# Slave.net
KiCad netlist of a schematic drawn in EAGLE
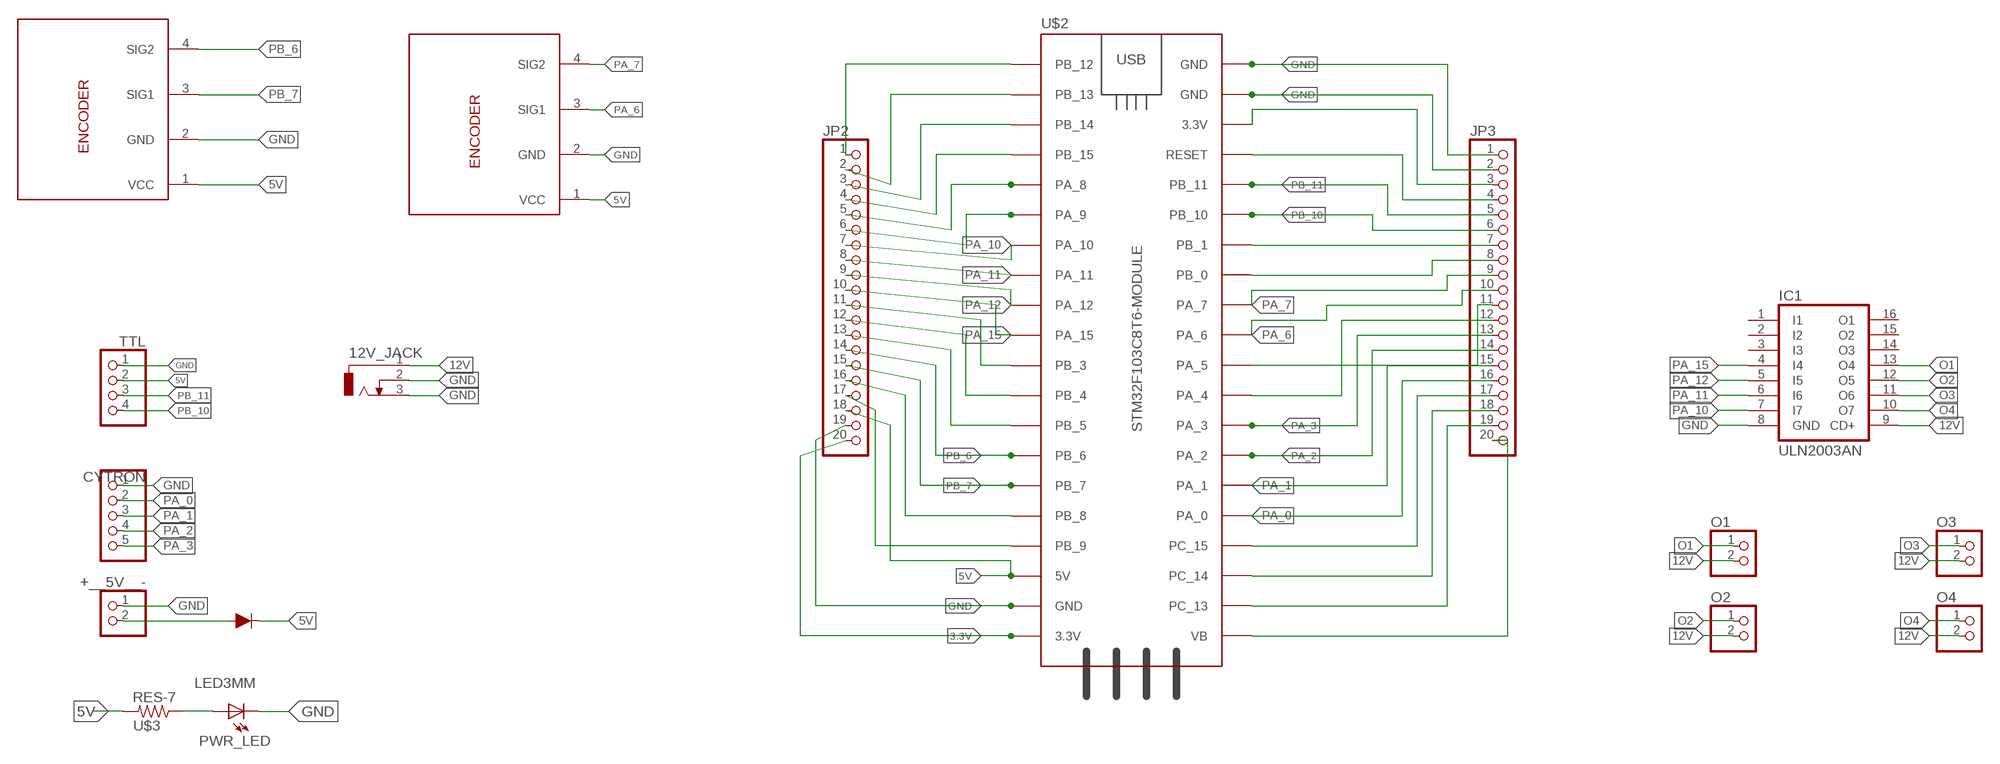
[diagram p0: schematic, sheet 1]

(export (version "E")
  (design (tool "Eeschema 10.0.6"))
  (components
    (comp (ref "+__5V__-")
      (value "PINHD-2_DATA")
      (footprint "eagle-import:1X02_DATA")
      (libsource (lib "eagle-import") (part "PINHD-2_DATA"))
    )
    (comp (ref "12V_JACK")
      (value "CON_JACK")
      (footprint "eagle-import:DCJ0303")
      (libsource (lib "eagle-import") (part "CON_JACK"))
    )
    (comp (ref "CYTRON")
      (value "PINHD-5_DATA")
      (footprint "eagle-import:1X05_DATA")
      (libsource (lib "eagle-import") (part "PINHD-5_DATA"))
    )
    (comp (ref "D1")
      (value "200mA/100V/1V")
      (footprint "eagle-import:DIODE-1N4148")
      (libsource (lib "eagle-import") (part "DIODE(1A)-1N4148"))
    )
    (comp (ref "IC1")
      (value "ULN2003AN")
      (footprint "eagle-import:DIL16")
      (libsource (lib "eagle-import") (part "ULN2003AN"))
    )
    (comp (ref "JP2")
      (value "PINHD-1X20")
      (footprint "eagle-import:1X20")
      (libsource (lib "eagle-import") (part "PINHD-1X20"))
    )
    (comp (ref "JP3")
      (value "PINHD-1X20")
      (footprint "eagle-import:1X20")
      (libsource (lib "eagle-import") (part "PINHD-1X20"))
    )
    (comp (ref "O1")
      (value "PINHD-2_DATA")
      (footprint "eagle-import:1X02_DATA")
      (libsource (lib "eagle-import") (part "PINHD-2_DATA"))
    )
    (comp (ref "O2")
      (value "PINHD-2_DATA")
      (footprint "eagle-import:1X02_DATA")
      (libsource (lib "eagle-import") (part "PINHD-2_DATA"))
    )
    (comp (ref "O3")
      (value "PINHD-2_DATA")
      (footprint "eagle-import:1X02_DATA")
      (libsource (lib "eagle-import") (part "PINHD-2_DATA"))
    )
    (comp (ref "O4")
      (value "PINHD-2_DATA")
      (footprint "eagle-import:1X02_DATA")
      (libsource (lib "eagle-import") (part "PINHD-2_DATA"))
    )
    (comp (ref "PWR_LED")
      (value "LED3MM")
      (footprint "eagle-import:LED3MM")
      (libsource (lib "eagle-import") (part "LED3MM"))
    )
    (comp (ref "TTL")
      (value "PINHD-4_DATA")
      (footprint "eagle-import:1X04_DATA")
      (libsource (lib "eagle-import") (part "PINHD-4_DATA"))
    )
    (comp (ref "U$1")
      (value "ENCODER")
      (footprint "eagle-import:1X04_DATA")
      (libsource (lib "eagle-import") (part "ENCODER"))
    )
    (comp (ref "U$2")
      (value "STM32F103C8T6-MODULE")
      (footprint "eagle-import:STM32F103C8T6-MODULE")
      (libsource (lib "eagle-import") (part "STM32F103C8T6-MODULE"))
    )
    (comp (ref "U$3")
      (value "RES-7")
      (footprint "eagle-import:0204_7")
      (libsource (lib "eagle-import") (part "RES-7"))
    )
    (comp (ref "U$5")
      (value "ENCODER")
      (footprint "eagle-import:1X04_DATA")
      (libsource (lib "eagle-import") (part "ENCODER"))
    )
  )
  (nets
    (net (code "1") (name "3.3V") (class "Default")
      (node (ref "JP2") (pin "20") (pinfunction "20_20") (pintype "passive"))
      (node (ref "U$2") (pin "3.3V_1") (pinfunction "3.3V_3.3V_1") (pintype "bidirectional"))
    )
    (net (code "2") (name "5V") (class "Default")
      (node (ref "D1") (pin "C") (pinfunction "C_C") (pintype "passive"))
      (node (ref "JP2") (pin "18") (pinfunction "18_18") (pintype "passive"))
      (node (ref "TTL") (pin "2") (pinfunction "2_2") (pintype "passive"))
      (node (ref "U$1") (pin "1") (pinfunction "VCC_1") (pintype "bidirectional"))
      (node (ref "U$2") (pin "5V") (pinfunction "5V_5V") (pintype "bidirectional"))
      (node (ref "U$3") (pin "2") (pinfunction "2_2") (pintype "passive"))
      (node (ref "U$5") (pin "1") (pinfunction "VCC_1") (pintype "bidirectional"))
    )
    (net (code "3") (name "12V") (class "Default")
      (node (ref "12V_JACK") (pin "1") (pinfunction "1_1") (pintype "passive"))
      (node (ref "IC1") (pin "9") (pinfunction "CD+_9") (pintype "passive"))
      (node (ref "O1") (pin "2") (pinfunction "2_2") (pintype "passive"))
      (node (ref "O2") (pin "2") (pinfunction "2_2") (pintype "passive"))
      (node (ref "O3") (pin "2") (pinfunction "2_2") (pintype "passive"))
      (node (ref "O4") (pin "2") (pinfunction "2_2") (pintype "passive"))
    )
    (net (code "4") (name "GND") (class "Default")
      (node (ref "+__5V__-") (pin "1") (pinfunction "1_1") (pintype "passive"))
      (node (ref "12V_JACK") (pin "2") (pinfunction "2_2") (pintype "passive"))
      (node (ref "12V_JACK") (pin "3") (pinfunction "3_3") (pintype "passive"))
      (node (ref "CYTRON") (pin "1") (pinfunction "1_1") (pintype "passive"))
      (node (ref "IC1") (pin "8") (pinfunction "GND_8") (pintype "power_in"))
      (node (ref "JP2") (pin "19") (pinfunction "19_19") (pintype "passive"))
      (node (ref "JP3") (pin "1") (pinfunction "1_1") (pintype "passive"))
      (node (ref "JP3") (pin "2") (pinfunction "2_2") (pintype "passive"))
      (node (ref "PWR_LED") (pin "K") (pinfunction "C_K") (pintype "passive"))
      (node (ref "TTL") (pin "1") (pinfunction "1_1") (pintype "passive"))
      (node (ref "U$1") (pin "2") (pinfunction "GND_2") (pintype "bidirectional"))
      (node (ref "U$2") (pin "GND_1") (pinfunction "GND_GND_1") (pintype "bidirectional"))
      (node (ref "U$2") (pin "GND_2") (pinfunction "GND_GND_2") (pintype "bidirectional"))
      (node (ref "U$2") (pin "GND_3") (pinfunction "GND_GND_3") (pintype "power_in"))
      (node (ref "U$5") (pin "2") (pinfunction "GND_2") (pintype "bidirectional"))
    )
    (net (code "5") (name "Net-(+__5V__--Pad2)") (class "Default")
      (node (ref "+__5V__-") (pin "2") (pinfunction "2_2") (pintype "passive"))
      (node (ref "D1") (pin "A") (pinfunction "A_A") (pintype "passive"))
    )
    (net (code "6") (name "Net-(JP2-Pad1)") (class "Default")
      (node (ref "JP2") (pin "1") (pinfunction "1_1") (pintype "passive"))
      (node (ref "U$2") (pin "PB_12") (pinfunction "PB_12_PB_12") (pintype "bidirectional"))
    )
    (net (code "7") (name "Net-(JP2-Pad2)") (class "Default")
      (node (ref "JP2") (pin "2") (pinfunction "2_2") (pintype "passive"))
      (node (ref "U$2") (pin "PB_13") (pinfunction "PB_13_PB_13") (pintype "bidirectional"))
    )
    (net (code "8") (name "Net-(JP2-Pad3)") (class "Default")
      (node (ref "JP2") (pin "3") (pinfunction "3_3") (pintype "passive"))
      (node (ref "U$2") (pin "PB_14") (pinfunction "PB_14_PB_14") (pintype "bidirectional"))
    )
    (net (code "9") (name "Net-(JP2-Pad4)") (class "Default")
      (node (ref "JP2") (pin "4") (pinfunction "4_4") (pintype "passive"))
      (node (ref "U$2") (pin "PB_15") (pinfunction "PB_15_PB_15") (pintype "bidirectional"))
    )
    (net (code "10") (name "Net-(JP2-Pad5)") (class "Default")
      (node (ref "JP2") (pin "5") (pinfunction "5_5") (pintype "passive"))
      (node (ref "U$2") (pin "PA_8") (pinfunction "PA_8_PA_8") (pintype "bidirectional"))
    )
    (net (code "11") (name "Net-(JP2-Pad6)") (class "Default")
      (node (ref "JP2") (pin "6") (pinfunction "6_6") (pintype "passive"))
      (node (ref "U$2") (pin "PA_9") (pinfunction "PA_9_PA_9") (pintype "bidirectional"))
    )
    (net (code "12") (name "Net-(JP2-Pad11)") (class "Default")
      (node (ref "JP2") (pin "11") (pinfunction "11_11") (pintype "passive"))
      (node (ref "U$2") (pin "PB_3") (pinfunction "PB_3_PB_3") (pintype "bidirectional"))
    )
    (net (code "13") (name "Net-(JP2-Pad12)") (class "Default")
      (node (ref "JP2") (pin "12") (pinfunction "12_12") (pintype "passive"))
      (node (ref "U$2") (pin "PB_4") (pinfunction "PB_4_PB_4") (pintype "bidirectional"))
    )
    (net (code "14") (name "Net-(JP2-Pad13)") (class "Default")
      (node (ref "JP2") (pin "13") (pinfunction "13_13") (pintype "passive"))
      (node (ref "U$2") (pin "PB_5") (pinfunction "PB_5_PB_5") (pintype "bidirectional"))
    )
    (net (code "15") (name "Net-(JP2-Pad16)") (class "Default")
      (node (ref "JP2") (pin "16") (pinfunction "16_16") (pintype "passive"))
      (node (ref "U$2") (pin "PB_8") (pinfunction "PB_8_PB_8") (pintype "bidirectional"))
    )
    (net (code "16") (name "Net-(JP2-Pad17)") (class "Default")
      (node (ref "JP2") (pin "17") (pinfunction "17_17") (pintype "passive"))
      (node (ref "U$2") (pin "PB_9") (pinfunction "PB_9_PB_9") (pintype "bidirectional"))
    )
    (net (code "17") (name "Net-(JP3-Pad3)") (class "Default")
      (node (ref "JP3") (pin "3") (pinfunction "3_3") (pintype "passive"))
      (node (ref "U$2") (pin "3.3V_2") (pinfunction "3.3V_3.3V_2") (pintype "bidirectional"))
    )
    (net (code "18") (name "Net-(JP3-Pad4)") (class "Default")
      (node (ref "JP3") (pin "4") (pinfunction "4_4") (pintype "passive"))
      (node (ref "U$2") (pin "RESET") (pinfunction "RESET_RESET") (pintype "bidirectional"))
    )
    (net (code "19") (name "Net-(JP3-Pad7)") (class "Default")
      (node (ref "JP3") (pin "7") (pinfunction "7_7") (pintype "passive"))
      (node (ref "U$2") (pin "PB_1") (pinfunction "PB_1_PB_1") (pintype "bidirectional"))
    )
    (net (code "20") (name "Net-(JP3-Pad8)") (class "Default")
      (node (ref "JP3") (pin "8") (pinfunction "8_8") (pintype "passive"))
      (node (ref "U$2") (pin "PB_0") (pinfunction "PB_0_PB_0") (pintype "bidirectional"))
    )
    (net (code "21") (name "Net-(JP3-Pad11)") (class "Default")
      (node (ref "JP3") (pin "11") (pinfunction "11_11") (pintype "passive"))
      (node (ref "U$2") (pin "PA_5") (pinfunction "PA_5_PA_5") (pintype "bidirectional"))
    )
    (net (code "22") (name "Net-(JP3-Pad12)") (class "Default")
      (node (ref "JP3") (pin "12") (pinfunction "12_12") (pintype "passive"))
      (node (ref "U$2") (pin "PA_4") (pinfunction "PA_4_PA_4") (pintype "bidirectional"))
    )
    (net (code "23") (name "Net-(JP3-Pad17)") (class "Default")
      (node (ref "JP3") (pin "17") (pinfunction "17_17") (pintype "passive"))
      (node (ref "U$2") (pin "PC_15") (pinfunction "PC_15_PC_15") (pintype "bidirectional"))
    )
    (net (code "24") (name "Net-(JP3-Pad18)") (class "Default")
      (node (ref "JP3") (pin "18") (pinfunction "18_18") (pintype "passive"))
      (node (ref "U$2") (pin "PC_14") (pinfunction "PC_14_PC_14") (pintype "bidirectional"))
    )
    (net (code "25") (name "Net-(JP3-Pad19)") (class "Default")
      (node (ref "JP3") (pin "19") (pinfunction "19_19") (pintype "passive"))
      (node (ref "U$2") (pin "PC_13") (pinfunction "PC_13_PC_13") (pintype "bidirectional"))
    )
    (net (code "26") (name "Net-(JP3-Pad20)") (class "Default")
      (node (ref "JP3") (pin "20") (pinfunction "20_20") (pintype "passive"))
      (node (ref "U$2") (pin "VB") (pinfunction "VB_VB") (pintype "bidirectional"))
    )
    (net (code "27") (name "Net-(PWR_LED-PadA)") (class "Default")
      (node (ref "PWR_LED") (pin "A") (pinfunction "A_A") (pintype "passive"))
      (node (ref "U$3") (pin "1") (pinfunction "1_1") (pintype "passive"))
    )
    (net (code "28") (name "O1") (class "Default")
      (node (ref "IC1") (pin "13") (pinfunction "O4_13") (pintype "open_collector"))
      (node (ref "O1") (pin "1") (pinfunction "1_1") (pintype "passive"))
    )
    (net (code "29") (name "O2") (class "Default")
      (node (ref "IC1") (pin "12") (pinfunction "O5_12") (pintype "open_collector"))
      (node (ref "O2") (pin "1") (pinfunction "1_1") (pintype "passive"))
    )
    (net (code "30") (name "O3") (class "Default")
      (node (ref "IC1") (pin "11") (pinfunction "O6_11") (pintype "open_collector"))
      (node (ref "O3") (pin "1") (pinfunction "1_1") (pintype "passive"))
    )
    (net (code "31") (name "O4") (class "Default")
      (node (ref "IC1") (pin "10") (pinfunction "O7_10") (pintype "open_collector"))
      (node (ref "O4") (pin "1") (pinfunction "1_1") (pintype "passive"))
    )
    (net (code "32") (name "PA_0") (class "Default")
      (node (ref "CYTRON") (pin "2") (pinfunction "2_2") (pintype "passive"))
      (node (ref "JP3") (pin "16") (pinfunction "16_16") (pintype "passive"))
      (node (ref "U$2") (pin "PA_0") (pinfunction "PA_0_PA_0") (pintype "bidirectional"))
    )
    (net (code "33") (name "PA_1") (class "Default")
      (node (ref "CYTRON") (pin "3") (pinfunction "3_3") (pintype "passive"))
      (node (ref "JP3") (pin "15") (pinfunction "15_15") (pintype "passive"))
      (node (ref "U$2") (pin "PA_1") (pinfunction "PA_1_PA_1") (pintype "bidirectional"))
    )
    (net (code "34") (name "PA_2") (class "Default")
      (node (ref "CYTRON") (pin "4") (pinfunction "4_4") (pintype "passive"))
      (node (ref "JP3") (pin "14") (pinfunction "14_14") (pintype "passive"))
      (node (ref "U$2") (pin "PA_2") (pinfunction "PA_2_PA_2") (pintype "bidirectional"))
    )
    (net (code "35") (name "PA_3") (class "Default")
      (node (ref "CYTRON") (pin "5") (pinfunction "5_5") (pintype "passive"))
      (node (ref "JP3") (pin "13") (pinfunction "13_13") (pintype "passive"))
      (node (ref "U$2") (pin "PA_3") (pinfunction "PA_3_PA_3") (pintype "bidirectional"))
    )
    (net (code "36") (name "PA_6") (class "Default")
      (node (ref "JP3") (pin "10") (pinfunction "10_10") (pintype "passive"))
      (node (ref "U$1") (pin "3") (pinfunction "SIG1_3") (pintype "bidirectional"))
      (node (ref "U$2") (pin "PA_6") (pinfunction "PA_6_PA_6") (pintype "bidirectional"))
    )
    (net (code "37") (name "PA_7") (class "Default")
      (node (ref "JP3") (pin "9") (pinfunction "9_9") (pintype "passive"))
      (node (ref "U$1") (pin "4") (pinfunction "SIG2_4") (pintype "bidirectional"))
      (node (ref "U$2") (pin "PA_7") (pinfunction "PA_7_PA_7") (pintype "bidirectional"))
    )
    (net (code "38") (name "PA_10") (class "Default")
      (node (ref "IC1") (pin "7") (pinfunction "I7_7") (pintype "input"))
      (node (ref "JP2") (pin "7") (pinfunction "7_7") (pintype "passive"))
      (node (ref "U$2") (pin "PA_10") (pinfunction "PA_10_PA_10") (pintype "bidirectional"))
    )
    (net (code "39") (name "PA_11") (class "Default")
      (node (ref "IC1") (pin "6") (pinfunction "I6_6") (pintype "input"))
      (node (ref "JP2") (pin "8") (pinfunction "8_8") (pintype "passive"))
      (node (ref "U$2") (pin "PA_11") (pinfunction "PA_11_PA_11") (pintype "bidirectional"))
    )
    (net (code "40") (name "PA_12") (class "Default")
      (node (ref "IC1") (pin "5") (pinfunction "I5_5") (pintype "input"))
      (node (ref "JP2") (pin "9") (pinfunction "9_9") (pintype "passive"))
      (node (ref "U$2") (pin "PA_12") (pinfunction "PA_12_PA_12") (pintype "bidirectional"))
    )
    (net (code "41") (name "PA_15") (class "Default")
      (node (ref "IC1") (pin "4") (pinfunction "I4_4") (pintype "input"))
      (node (ref "JP2") (pin "10") (pinfunction "10_10") (pintype "passive"))
      (node (ref "U$2") (pin "PA_15") (pinfunction "PA_15_PA_15") (pintype "bidirectional"))
    )
    (net (code "42") (name "PB_6") (class "Default")
      (node (ref "JP2") (pin "14") (pinfunction "14_14") (pintype "passive"))
      (node (ref "U$2") (pin "PB_6") (pinfunction "PB_6_PB_6") (pintype "bidirectional"))
      (node (ref "U$5") (pin "4") (pinfunction "SIG2_4") (pintype "bidirectional"))
    )
    (net (code "43") (name "PB_7") (class "Default")
      (node (ref "JP2") (pin "15") (pinfunction "15_15") (pintype "passive"))
      (node (ref "U$2") (pin "PB_7") (pinfunction "PB_7_PB_7") (pintype "bidirectional"))
      (node (ref "U$5") (pin "3") (pinfunction "SIG1_3") (pintype "bidirectional"))
    )
    (net (code "44") (name "PB_10") (class "Default")
      (node (ref "JP3") (pin "6") (pinfunction "6_6") (pintype "passive"))
      (node (ref "TTL") (pin "4") (pinfunction "4_4") (pintype "passive"))
      (node (ref "U$2") (pin "PB_10") (pinfunction "PB_10_PB_10") (pintype "bidirectional"))
    )
    (net (code "45") (name "PB_11") (class "Default")
      (node (ref "JP3") (pin "5") (pinfunction "5_5") (pintype "passive"))
      (node (ref "TTL") (pin "3") (pinfunction "3_3") (pintype "passive"))
      (node (ref "U$2") (pin "PB_11") (pinfunction "PB_11_PB_11") (pintype "bidirectional"))
    )
    (net (code "46") (name "unconnected-(IC1-I1-Pad1)") (class "Default")
      (node (ref "IC1") (pin "1") (pinfunction "I1_1") (pintype "input"))
    )
    (net (code "47") (name "unconnected-(IC1-I2-Pad2)") (class "Default")
      (node (ref "IC1") (pin "2") (pinfunction "I2_2") (pintype "input"))
    )
    (net (code "48") (name "unconnected-(IC1-I3-Pad3)") (class "Default")
      (node (ref "IC1") (pin "3") (pinfunction "I3_3") (pintype "input"))
    )
    (net (code "49") (name "unconnected-(IC1-O1-Pad16)") (class "Default")
      (node (ref "IC1") (pin "16") (pinfunction "O1_16") (pintype "open_collector"))
    )
    (net (code "50") (name "unconnected-(IC1-O2-Pad15)") (class "Default")
      (node (ref "IC1") (pin "15") (pinfunction "O2_15") (pintype "open_collector"))
    )
    (net (code "51") (name "unconnected-(IC1-O3-Pad14)") (class "Default")
      (node (ref "IC1") (pin "14") (pinfunction "O3_14") (pintype "open_collector"))
    )
  )
)
